# 02_RF.net
KiCad netlist of a schematic drawn in Altium Designer
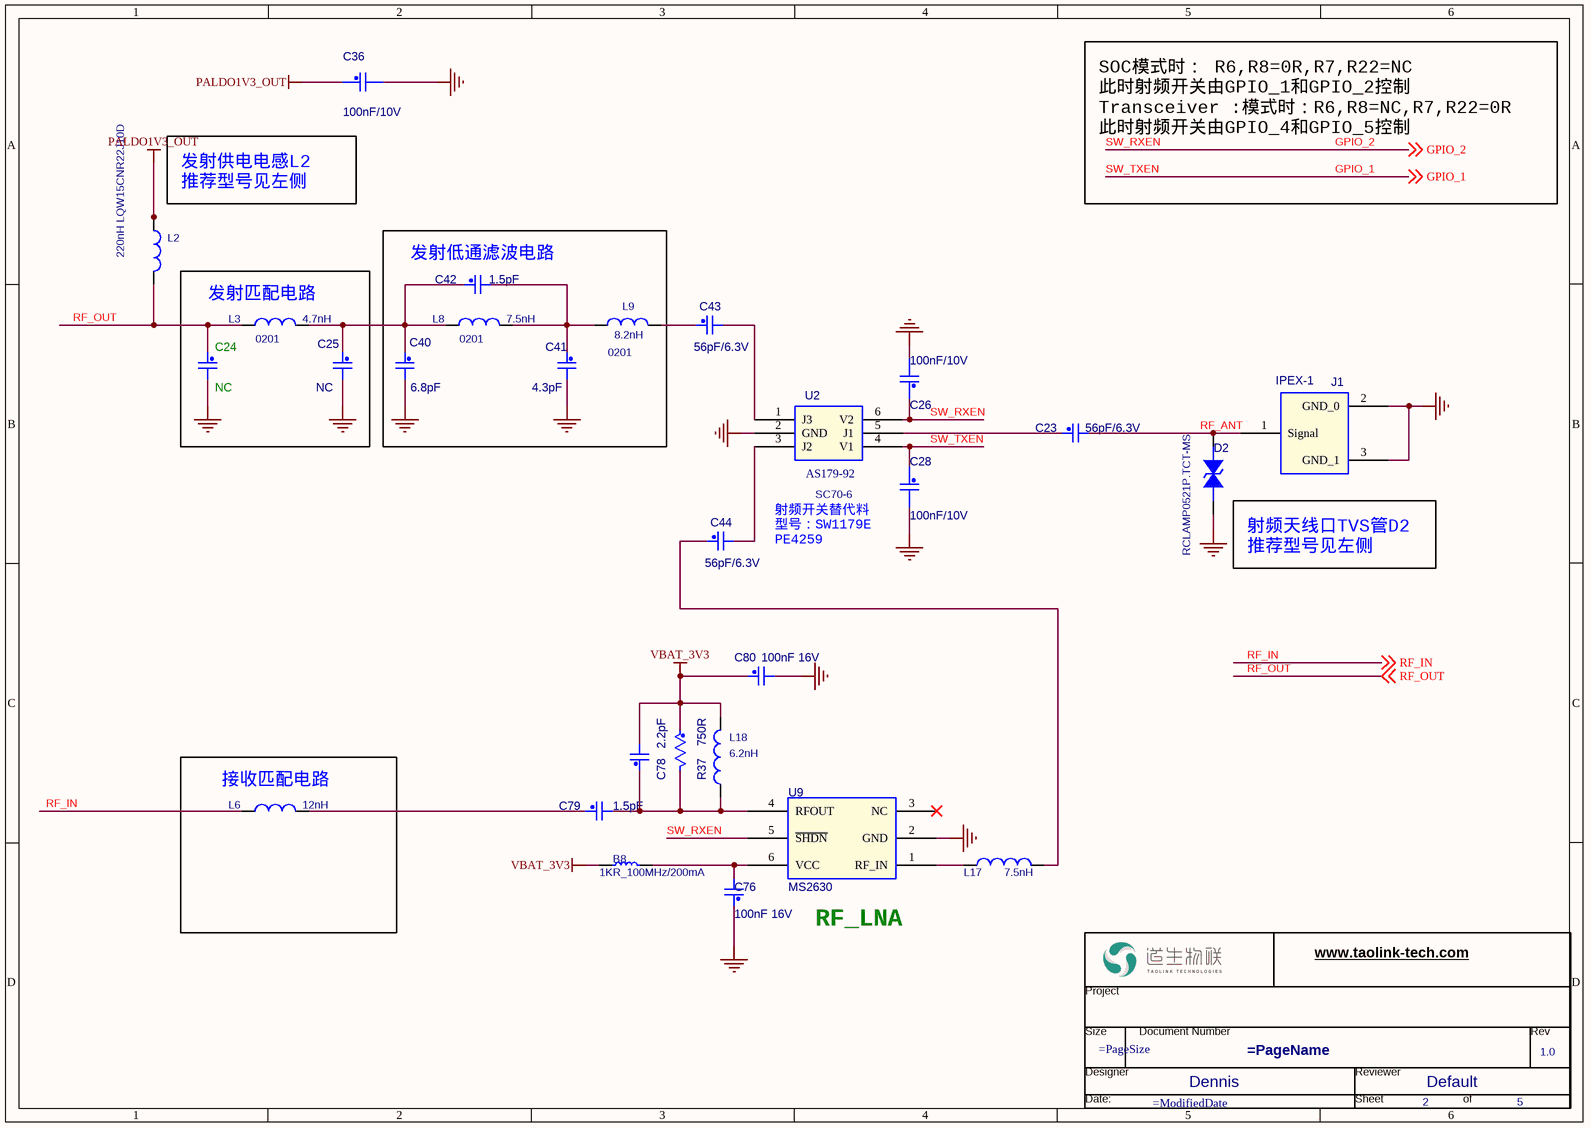
[diagram p0: 02_RF.SchDoc]

(export (version "E")
  (design (tool "Eeschema 10.0.6"))
  (components
    (comp (ref "B8")
      (value "1KR_100MHz/200mA")
      (footprint "0201")
      (fields (field (name "REVIEWED2") "LBY"))
      (libsource (lib "*") (part "INDUCTOR_Dup1"))
    )
    (comp (ref "C23")
      (value "56pF/6.3V")
      (footprint "0201")
      (description "Ceramic Capacitor,22uF,6.3V,+/-20%,X5R,0603,Samsung")
      (fields (field (name "MANUFACTURER") "Samsung"))
      (libsource (lib "*") (part "Ceramic Capacitor"))
    )
    (comp (ref "C24")
      (value "NC")
      (footprint "0201")
      (description "Ceramic Capacitor,22uF,6.3V,+/-20%,X5R,0603,Samsung")
      (fields (field (name "MANUFACTURER") "Samsung"))
      (libsource (lib "*") (part "Ceramic Capacitor"))
    )
    (comp (ref "C25")
      (value "NC")
      (footprint "0201")
      (description "Ceramic Capacitor,22uF,6.3V,+/-20%,X5R,0603,Samsung")
      (fields (field (name "MANUFACTURER") "Samsung"))
      (libsource (lib "*") (part "Ceramic Capacitor"))
    )
    (comp (ref "C26")
      (value "100nF/10V")
      (footprint "0201")
      (description "Ceramic Capacitor,100nF,50V,+/-10%,X7R,0402,Fenghua")
      (fields (field (name "MANUFACTURER") "Fenghua"))
      (libsource (lib "*") (part "Ceramic Capacitor_14"))
    )
    (comp (ref "C28")
      (value "100nF/10V")
      (footprint "0201")
      (description "Ceramic Capacitor,100nF,50V,+/-10%,X7R,0402,Fenghua")
      (fields (field (name "MANUFACTURER") "Fenghua"))
      (libsource (lib "*") (part "Ceramic Capacitor_14"))
    )
    (comp (ref "C36")
      (value "100nF/10V")
      (footprint "0201")
      (description "Ceramic Capacitor,100nF,50V,+/-10%,X7R,0402,Fenghua")
      (fields (field (name "MANUFACTURER") "Fenghua"))
      (libsource (lib "*") (part "Ceramic Capacitor_14"))
    )
    (comp (ref "C40")
      (value "6.8pF")
      (footprint "0201")
      (description "Ceramic Capacitor,22uF,6.3V,+/-20%,X5R,0603,Samsung")
      (fields (field (name "MANUFACTURER") "Samsung"))
      (libsource (lib "*") (part "Ceramic Capacitor"))
    )
    (comp (ref "C41")
      (value "4.3pF")
      (footprint "0201")
      (description "Ceramic Capacitor,22uF,6.3V,+/-20%,X5R,0603,Samsung")
      (fields (field (name "MANUFACTURER") "Samsung"))
      (libsource (lib "*") (part "Ceramic Capacitor"))
    )
    (comp (ref "C42")
      (value "1.5pF")
      (footprint "0201")
      (description "Ceramic Capacitor,22uF,6.3V,+/-20%,X5R,0603,Samsung")
      (fields (field (name "MANUFACTURER") "Samsung"))
      (libsource (lib "*") (part "Ceramic Capacitor"))
    )
    (comp (ref "C43")
      (value "56pF/6.3V")
      (footprint "0201")
      (description "Ceramic Capacitor,22uF,6.3V,+/-20%,X5R,0603,Samsung")
      (fields (field (name "MANUFACTURER") "Samsung"))
      (libsource (lib "*") (part "Ceramic Capacitor"))
    )
    (comp (ref "C44")
      (value "56pF/6.3V")
      (footprint "0201")
      (description "Ceramic Capacitor,22uF,6.3V,+/-20%,X5R,0603,Samsung")
      (fields (field (name "MANUFACTURER") "Samsung"))
      (libsource (lib "*") (part "Ceramic Capacitor"))
    )
    (comp (ref "C76")
      (value "100nF 16V")
      (footprint "0201")
      (description "Ceramic Capacitor,22uF,6.3V,+/-20%,X5R,0603,Samsung")
      (fields (field (name "MANUFACTURER") "Samsung"))
      (libsource (lib "*") (part "Ceramic Capacitor"))
    )
    (comp (ref "C78")
      (value "2.2pF")
      (footprint "0201")
      (description "Ceramic Capacitor,22uF,6.3V,+/-20%,X5R,0603,Samsung")
      (fields (field (name "MANUFACTURER") "Samsung"))
      (libsource (lib "*") (part "Ceramic Capacitor"))
    )
    (comp (ref "C79")
      (value "1.5pF")
      (footprint "0201")
      (description "Ceramic Capacitor,22uF,6.3V,+/-20%,X5R,0603,Samsung")
      (fields (field (name "MANUFACTURER") "Samsung"))
      (libsource (lib "*") (part "Ceramic Capacitor"))
    )
    (comp (ref "C80")
      (value "100nF 16V")
      (footprint "0201")
      (description "Ceramic Capacitor,22uF,6.3V,+/-20%,X5R,0603,Samsung")
      (fields (field (name "MANUFACTURER") "Samsung"))
      (libsource (lib "*") (part "Ceramic Capacitor"))
    )
    (comp (ref "D2") (value "RCLAMP0521P.TCT-MS") (footprint "TVS-0402") (libsource (lib "*") (part "TVS")))
    (comp (ref "J1") (value "IPEX-1") (footprint "IPEX-1") (libsource (lib "*") (part "IPEX-1")))
    (comp (ref "L2")
      (value "220nH LQW15CNR22J10D")
      (footprint "L0402")
      (libsource (lib "*") (part "INDUCTOR_Dup2"))
    )
    (comp (ref "L3")
      (value "4.7nH")
      (footprint "0201")
      (fields (field (name "PCB FOOTPRINT") "0201"))
      (libsource (lib "*") (part "INDUCTOR_Dup2"))
    )
    (comp (ref "L6") (value "12nH") (footprint "0201") (libsource (lib "*") (part "INDUCTOR_Dup2")))
    (comp (ref "L8")
      (value "7.5nH")
      (footprint "0201")
      (fields (field (name "PCB FOOTPRINT") "0201"))
      (libsource (lib "*") (part "INDUCTOR_Dup2"))
    )
    (comp (ref "L9")
      (value "8.2nH")
      (footprint "0201")
      (fields (field (name "PCB FOOTPRINT") "0201"))
      (libsource (lib "*") (part "INDUCTOR_Dup2"))
    )
    (comp (ref "L17") (value "7.5nH") (footprint "0201") (libsource (lib "*") (part "INDUCTOR")))
    (comp (ref "L18") (value "6.2nH") (footprint "0201") (libsource (lib "*") (part "INDUCTOR")))
    (comp (ref "R37")
      (value "750R")
      (footprint "0201")
      (description "Thick Film Resistor,0R,+/-5%,1/16W,-55°C ~ 155°C,SMD,0402,Fenghua")
      (fields (field (name "MANUFACTURER") "Fenghua"))
      (libsource (lib "*") (part "Resister"))
    )
    (comp (ref "U2")
      (value "AS179-92")
      (footprint "SC70-6")
      (fields (field (name "PCB FOOTPRINT") "SC70-6"))
      (libsource (lib "*") (part "AS179-92"))
    )
    (comp (ref "U9") (value "MS2630") (footprint "SOT23-6") (libsource (lib "*") (part "MS2630")))
  )
  (nets
    (net (code "1") (name "/RF_ANT") (class "Default")
      (node (ref "C23") (pin "2") (pinfunction "2_2") (pintype "passive"))
      (node (ref "D2") (pin "1") (pinfunction "ANODE_1") (pintype "passive"))
      (node (ref "J1") (pin "1") (pinfunction "Signal_1") (pintype "passive"))
    )
    (net (code "2") (name "GND") (class "Default")
      (node (ref "C24") (pin "2") (pinfunction "2_2") (pintype "passive"))
      (node (ref "C25") (pin "2") (pinfunction "2_2") (pintype "passive"))
      (node (ref "C26") (pin "2") (pinfunction "2_2") (pintype "passive"))
      (node (ref "C28") (pin "2") (pinfunction "2_2") (pintype "passive"))
      (node (ref "C36") (pin "2") (pinfunction "2_2") (pintype "passive"))
      (node (ref "C40") (pin "2") (pinfunction "2_2") (pintype "passive"))
      (node (ref "C41") (pin "2") (pinfunction "2_2") (pintype "passive"))
      (node (ref "C76") (pin "1") (pinfunction "1_1") (pintype "passive"))
      (node (ref "C80") (pin "2") (pinfunction "2_2") (pintype "passive"))
      (node (ref "D2") (pin "2") (pinfunction "CATHODE_2") (pintype "passive"))
      (node (ref "J1") (pin "2") (pinfunction "GND_0_2") (pintype "passive"))
      (node (ref "J1") (pin "3") (pinfunction "GND_1_3") (pintype "passive"))
      (node (ref "U2") (pin "2") (pinfunction "GND_2") (pintype "passive"))
      (node (ref "U9") (pin "2") (pinfunction "GND_2") (pintype "passive"))
    )
    (net (code "3") (name "GPIO_1") (class "Default")
      (node (ref "C28") (pin "1") (pinfunction "1_1") (pintype "passive"))
      (node (ref "U2") (pin "4") (pinfunction "V1_4") (pintype "passive"))
    )
    (net (code "4") (name "GPIO_2") (class "Default")
      (node (ref "C26") (pin "1") (pinfunction "1_1") (pintype "passive"))
      (node (ref "U2") (pin "6") (pinfunction "V2_6") (pintype "passive"))
      (node (ref "U9") (pin "5") (pinfunction "~{SHDN}_5") (pintype "passive"))
    )
    (net (code "5") (name "Net-(C25-Pad1)") (class "Default")
      (node (ref "C25") (pin "1") (pinfunction "1_1") (pintype "passive"))
      (node (ref "C40") (pin "1") (pinfunction "1_1") (pintype "passive"))
      (node (ref "C42") (pin "1") (pinfunction "1_1") (pintype "passive"))
      (node (ref "L3") (pin "2") (pinfunction "2_2") (pintype "passive"))
      (node (ref "L8") (pin "1") (pinfunction "1_1") (pintype "passive"))
    )
    (net (code "6") (name "Net-(C41-Pad1)") (class "Default")
      (node (ref "C41") (pin "1") (pinfunction "1_1") (pintype "passive"))
      (node (ref "C42") (pin "2") (pinfunction "2_2") (pintype "passive"))
      (node (ref "L8") (pin "2") (pinfunction "2_2") (pintype "passive"))
      (node (ref "L9") (pin "1") (pinfunction "1_1") (pintype "passive"))
    )
    (net (code "7") (name "Net-(C43-Pad1)") (class "Default")
      (node (ref "C43") (pin "1") (pinfunction "1_1") (pintype "passive"))
      (node (ref "L9") (pin "2") (pinfunction "2_2") (pintype "passive"))
    )
    (net (code "8") (name "Net-(C44-Pad1)") (class "Default")
      (node (ref "C44") (pin "1") (pinfunction "1_1") (pintype "passive"))
      (node (ref "L17") (pin "2") (pinfunction "2_2") (pintype "passive"))
    )
    (net (code "9") (name "Net-(C79-Pad1)") (class "Default")
      (node (ref "C79") (pin "1") (pinfunction "1_1") (pintype "passive"))
      (node (ref "L6") (pin "2") (pinfunction "2_2") (pintype "passive"))
    )
    (net (code "10") (name "Net-(U2-J1)") (class "Default")
      (node (ref "C23") (pin "1") (pinfunction "1_1") (pintype "passive"))
      (node (ref "U2") (pin "5") (pinfunction "J1_5") (pintype "passive"))
    )
    (net (code "11") (name "Net-(U2-J2)") (class "Default")
      (node (ref "C44") (pin "2") (pinfunction "2_2") (pintype "passive"))
      (node (ref "U2") (pin "3") (pinfunction "J2_3") (pintype "passive"))
    )
    (net (code "12") (name "Net-(U2-J3)") (class "Default")
      (node (ref "C43") (pin "2") (pinfunction "2_2") (pintype "passive"))
      (node (ref "U2") (pin "1") (pinfunction "J3_1") (pintype "passive"))
    )
    (net (code "13") (name "Net-(U9-RFOUT)") (class "Default")
      (node (ref "C78") (pin "1") (pinfunction "1_1") (pintype "passive"))
      (node (ref "C79") (pin "2") (pinfunction "2_2") (pintype "passive"))
      (node (ref "L18") (pin "1") (pinfunction "1_1") (pintype "passive"))
      (node (ref "R37") (pin "2") (pinfunction "2_2") (pintype "passive"))
      (node (ref "U9") (pin "4") (pinfunction "RFOUT_4") (pintype "passive"))
    )
    (net (code "14") (name "Net-(U9-RF_IN)") (class "Default")
      (node (ref "L17") (pin "1") (pinfunction "1_1") (pintype "passive"))
      (node (ref "U9") (pin "1") (pinfunction "RF_IN_1") (pintype "passive"))
    )
    (net (code "15") (name "Net-(U9-VCC)") (class "Default")
      (node (ref "B8") (pin "1") (pinfunction "1_1") (pintype "passive"))
      (node (ref "C76") (pin "2") (pinfunction "2_2") (pintype "passive"))
      (node (ref "U9") (pin "6") (pinfunction "VCC_6") (pintype "passive"))
    )
    (net (code "16") (name "PALDO1V3_OUT") (class "Default")
      (node (ref "C36") (pin "1") (pinfunction "1_1") (pintype "passive"))
      (node (ref "L2") (pin "1") (pinfunction "1_1") (pintype "passive"))
    )
    (net (code "17") (name "RF_IN") (class "Default")
      (node (ref "L6") (pin "1") (pinfunction "1_1") (pintype "passive"))
    )
    (net (code "18") (name "RF_OUT") (class "Default")
      (node (ref "C24") (pin "1") (pinfunction "1_1") (pintype "passive"))
      (node (ref "L2") (pin "2") (pinfunction "2_2") (pintype "passive"))
      (node (ref "L3") (pin "1") (pinfunction "1_1") (pintype "passive"))
    )
    (net (code "19") (name "VBAT_3V3") (class "Default")
      (node (ref "B8") (pin "2") (pinfunction "2_2") (pintype "passive"))
      (node (ref "C78") (pin "2") (pinfunction "2_2") (pintype "passive"))
      (node (ref "C80") (pin "1") (pinfunction "1_1") (pintype "passive"))
      (node (ref "L18") (pin "2") (pinfunction "2_2") (pintype "passive"))
      (node (ref "R37") (pin "1") (pinfunction "1_1") (pintype "passive"))
    )
    (net (code "20") (name "unconnected-(U9-NC-Pad3)") (class "Default")
      (node (ref "U9") (pin "3") (pinfunction "NC_3") (pintype "passive+no_connect"))
    )
  )
)
